# crt13n.net
KiCad netlist of a schematic drawn in EAGLE
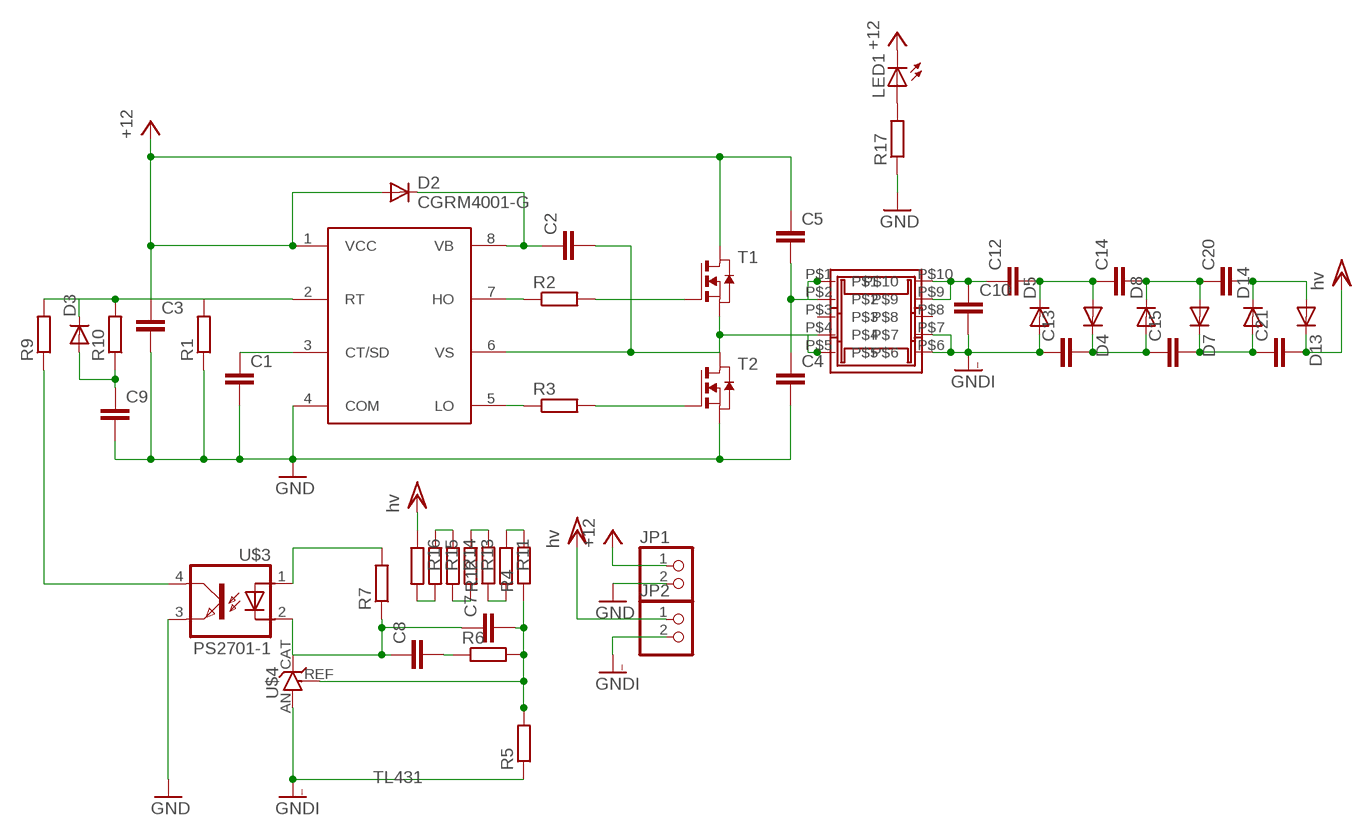
[diagram p0: schematic, sheet 1]

(export (version "E")
  (design (tool "Eeschema 10.0.6"))
  (components
    (comp (ref "C1")
      (value "C-EUC0805")
      (footprint "eagle-import:C0805")
      (libsource (lib "eagle-import") (part "C-EUC0805"))
    )
    (comp (ref "C2")
      (value "C-EUC0805")
      (footprint "eagle-import:C0805")
      (libsource (lib "eagle-import") (part "C-EUC0805"))
    )
    (comp (ref "C3")
      (value "C-EUC1206")
      (footprint "eagle-import:C1206")
      (libsource (lib "eagle-import") (part "C-EUC1206"))
    )
    (comp (ref "C4")
      (value "CC1206")
      (footprint "eagle-import:C1206")
      (libsource (lib "eagle-import") (part "CC1206"))
    )
    (comp (ref "C5")
      (value "CC1206")
      (footprint "eagle-import:C1206")
      (libsource (lib "eagle-import") (part "CC1206"))
    )
    (comp (ref "C7")
      (value "C-EUC0805")
      (footprint "eagle-import:C0805")
      (libsource (lib "eagle-import") (part "C-EUC0805"))
    )
    (comp (ref "C8")
      (value "C-EUC0805")
      (footprint "eagle-import:C0805")
      (libsource (lib "eagle-import") (part "C-EUC0805"))
    )
    (comp (ref "C9")
      (value "C-EUC1206")
      (footprint "eagle-import:C1206")
      (libsource (lib "eagle-import") (part "C-EUC1206"))
    )
    (comp (ref "C10")
      (value "C-EUC1812")
      (footprint "eagle-import:C1812")
      (libsource (lib "eagle-import") (part "C-EUC1812"))
    )
    (comp (ref "C12")
      (value "C-EUC2220K")
      (footprint "eagle-import:C2220K")
      (libsource (lib "eagle-import") (part "C-EUC2220K"))
    )
    (comp (ref "C13")
      (value "C-EUC2220K")
      (footprint "eagle-import:C2220K")
      (libsource (lib "eagle-import") (part "C-EUC2220K"))
    )
    (comp (ref "C14")
      (value "C-EUC2220K")
      (footprint "eagle-import:C2220K")
      (libsource (lib "eagle-import") (part "C-EUC2220K"))
    )
    (comp (ref "C15")
      (value "C-EUC2220K")
      (footprint "eagle-import:C2220K")
      (libsource (lib "eagle-import") (part "C-EUC2220K"))
    )
    (comp (ref "C20")
      (value "C-EUC2220K")
      (footprint "eagle-import:C2220K")
      (libsource (lib "eagle-import") (part "C-EUC2220K"))
    )
    (comp (ref "C21")
      (value "C-EUC2220K")
      (footprint "eagle-import:C2220K")
      (libsource (lib "eagle-import") (part "C-EUC2220K"))
    )
    (comp (ref "D2")
      (value "CGRM4001-G")
      (footprint "eagle-import:SOD-123_MINI-SMA")
      (libsource (lib "eagle-import") (part "CGRM400-G1"))
    )
    (comp (ref "D3")
      (value "DIODE-SOD80C")
      (footprint "eagle-import:SOD80C")
      (libsource (lib "eagle-import") (part "DIODE-SOD80C"))
    )
    (comp (ref "D4")
      (value "DIODE-DO-214AC")
      (footprint "eagle-import:DO-214AC")
      (libsource (lib "eagle-import") (part "DIODE-DO-214AC"))
    )
    (comp (ref "D5")
      (value "DIODE-DO-214AC")
      (footprint "eagle-import:DO-214AC")
      (libsource (lib "eagle-import") (part "DIODE-DO-214AC"))
    )
    (comp (ref "D7")
      (value "DIODE-DO-214AC")
      (footprint "eagle-import:DO-214AC")
      (libsource (lib "eagle-import") (part "DIODE-DO-214AC"))
    )
    (comp (ref "D8")
      (value "DIODE-DO-214AC")
      (footprint "eagle-import:DO-214AC")
      (libsource (lib "eagle-import") (part "DIODE-DO-214AC"))
    )
    (comp (ref "D13")
      (value "DIODE-DO-214AC")
      (footprint "eagle-import:DO-214AC")
      (libsource (lib "eagle-import") (part "DIODE-DO-214AC"))
    )
    (comp (ref "D14")
      (value "DIODE-DO-214AC")
      (footprint "eagle-import:DO-214AC")
      (libsource (lib "eagle-import") (part "DIODE-DO-214AC"))
    )
    (comp (ref "JP1")
      (value "PINHD-1X2")
      (footprint "eagle-import:1X02")
      (libsource (lib "eagle-import") (part "PINHD-1X2"))
    )
    (comp (ref "JP2")
      (value "PINHD-1X2")
      (footprint "eagle-import:1X02")
      (libsource (lib "eagle-import") (part "PINHD-1X2"))
    )
    (comp (ref "LED1")
      (value "LEDCHIP-LED0805")
      (footprint "eagle-import:CHIP-LED0805")
      (libsource (lib "eagle-import") (part "LEDCHIP-LED0805"))
    )
    (comp (ref "R1")
      (value "R-EU_R0805")
      (footprint "eagle-import:R0805")
      (libsource (lib "eagle-import") (part "R-EU_R0805"))
    )
    (comp (ref "R2")
      (value "R-EU_R0805")
      (footprint "eagle-import:R0805")
      (libsource (lib "eagle-import") (part "R-EU_R0805"))
    )
    (comp (ref "R3")
      (value "R-EU_R0805")
      (footprint "eagle-import:R0805")
      (libsource (lib "eagle-import") (part "R-EU_R0805"))
    )
    (comp (ref "R4")
      (value "R-EU_R0805")
      (footprint "eagle-import:R0805")
      (libsource (lib "eagle-import") (part "R-EU_R0805"))
    )
    (comp (ref "R5")
      (value "R-EU_R0805")
      (footprint "eagle-import:R0805")
      (libsource (lib "eagle-import") (part "R-EU_R0805"))
    )
    (comp (ref "R6")
      (value "R-EU_R0805")
      (footprint "eagle-import:R0805")
      (libsource (lib "eagle-import") (part "R-EU_R0805"))
    )
    (comp (ref "R7")
      (value "R-EU_R0805")
      (footprint "eagle-import:R0805")
      (libsource (lib "eagle-import") (part "R-EU_R0805"))
    )
    (comp (ref "R9")
      (value "R-EU_R0805")
      (footprint "eagle-import:R0805")
      (libsource (lib "eagle-import") (part "R-EU_R0805"))
    )
    (comp (ref "R10")
      (value "R-EU_R0805")
      (footprint "eagle-import:R0805")
      (libsource (lib "eagle-import") (part "R-EU_R0805"))
    )
    (comp (ref "R11")
      (value "R-EU_R0805")
      (footprint "eagle-import:R0805")
      (libsource (lib "eagle-import") (part "R-EU_R0805"))
    )
    (comp (ref "R12")
      (value "R-EU_R0805")
      (footprint "eagle-import:R0805")
      (libsource (lib "eagle-import") (part "R-EU_R0805"))
    )
    (comp (ref "R13")
      (value "R-EU_R0805")
      (footprint "eagle-import:R0805")
      (libsource (lib "eagle-import") (part "R-EU_R0805"))
    )
    (comp (ref "R14")
      (value "R-EU_R0805")
      (footprint "eagle-import:R0805")
      (libsource (lib "eagle-import") (part "R-EU_R0805"))
    )
    (comp (ref "R15")
      (value "R-EU_R0805")
      (footprint "eagle-import:R0805")
      (libsource (lib "eagle-import") (part "R-EU_R0805"))
    )
    (comp (ref "R16")
      (value "R-EU_R0805")
      (footprint "eagle-import:R0805")
      (libsource (lib "eagle-import") (part "R-EU_R0805"))
    )
    (comp (ref "R17")
      (value "R-EU_R0805")
      (footprint "eagle-import:R0805")
      (libsource (lib "eagle-import") (part "R-EU_R0805"))
    )
    (comp (ref "T1")
      (value "NMOSSOT23")
      (footprint "eagle-import:SOT-23")
      (libsource (lib "eagle-import") (part "NMOSSOT23"))
    )
    (comp (ref "T2")
      (value "NMOSSOT23")
      (footprint "eagle-import:SOT-23")
      (libsource (lib "eagle-import") (part "NMOSSOT23"))
    )
    (comp (ref "U$1")
      (value "IRS2795")
      (footprint "eagle-import:SO08")
      (libsource (lib "eagle-import") (part "IRS2795"))
    )
    (comp (ref "U$2")
      (value "EFD15-K-10P")
      (footprint "eagle-import:EFD15-K10P")
      (libsource (lib "eagle-import") (part "EFD15-K-10P"))
    )
    (comp (ref "U$3")
      (value "PS2701-1")
      (footprint "eagle-import:SOP04")
      (libsource (lib "eagle-import") (part "PS2701-1"))
    )
    (comp (ref "U$4")
      (value "TL431")
      (footprint "eagle-import:SOT23")
      (libsource (lib "eagle-import") (part "TL431"))
    )
  )
  (nets
    (net (code "1") (name "+12") (class "Default")
      (node (ref "C3") (pin "1") (pinfunction "1_1") (pintype "passive"))
      (node (ref "C5") (pin "1") (pinfunction "1_1") (pintype "passive"))
      (node (ref "D2") (pin "A") (pinfunction "A_A") (pintype "passive"))
      (node (ref "JP1") (pin "1") (pinfunction "1_1") (pintype "passive"))
      (node (ref "LED1") (pin "C") (pinfunction "C_C") (pintype "passive"))
      (node (ref "T1") (pin "1") (pinfunction "D_1") (pintype "passive"))
      (node (ref "U$1") (pin "1") (pinfunction "VCC_1") (pintype "bidirectional"))
    )
    (net (code "2") (name "GND") (class "Default")
      (node (ref "C1") (pin "2") (pinfunction "2_2") (pintype "passive"))
      (node (ref "C3") (pin "2") (pinfunction "2_2") (pintype "passive"))
      (node (ref "C4") (pin "2") (pinfunction "2_2") (pintype "passive"))
      (node (ref "C9") (pin "2") (pinfunction "2_2") (pintype "passive"))
      (node (ref "JP1") (pin "2") (pinfunction "2_2") (pintype "passive"))
      (node (ref "R1") (pin "1") (pinfunction "1_1") (pintype "passive"))
      (node (ref "R17") (pin "1") (pinfunction "1_1") (pintype "passive"))
      (node (ref "T2") (pin "2") (pinfunction "S_2") (pintype "passive"))
      (node (ref "U$1") (pin "4") (pinfunction "COM_4") (pintype "bidirectional"))
      (node (ref "U$3") (pin "3") (pinfunction "3_3") (pintype "passive"))
    )
    (net (code "3") (name "GNDI") (class "Default")
      (node (ref "C10") (pin "2") (pinfunction "2_2") (pintype "passive"))
      (node (ref "C13") (pin "1") (pinfunction "1_1") (pintype "passive"))
      (node (ref "D5") (pin "A") (pinfunction "A_A") (pintype "passive"))
      (node (ref "JP2") (pin "2") (pinfunction "2_2") (pintype "passive"))
      (node (ref "R5") (pin "1") (pinfunction "1_1") (pintype "passive"))
      (node (ref "U$2") (pin "P$6") (pinfunction "P$6_P$6") (pintype "bidirectional"))
      (node (ref "U$2") (pin "P$7") (pinfunction "P$7_P$7") (pintype "bidirectional"))
      (node (ref "U$4") (pin "AN") (pinfunction "AN_AN") (pintype "passive"))
    )
    (net (code "4") (name "Net-(C4-Pad1)") (class "Default")
      (node (ref "C4") (pin "1") (pinfunction "1_1") (pintype "passive"))
      (node (ref "C5") (pin "2") (pinfunction "2_2") (pintype "passive"))
      (node (ref "U$2") (pin "P$1") (pinfunction "P$1_P$1") (pintype "bidirectional"))
      (node (ref "U$2") (pin "P$2") (pinfunction "P$2_P$2") (pintype "bidirectional"))
    )
    (net (code "5") (name "Net-(C7-Pad1)") (class "Default")
      (node (ref "C7") (pin "1") (pinfunction "1_1") (pintype "passive"))
      (node (ref "C8") (pin "1") (pinfunction "1_1") (pintype "passive"))
      (node (ref "R7") (pin "1") (pinfunction "1_1") (pintype "passive"))
      (node (ref "U$3") (pin "2") (pinfunction "2_2") (pintype "passive"))
      (node (ref "U$4") (pin "CAT") (pinfunction "CAT_CAT") (pintype "passive"))
    )
    (net (code "6") (name "Net-(C7-Pad2)") (class "Default")
      (node (ref "C7") (pin "2") (pinfunction "2_2") (pintype "passive"))
      (node (ref "R4") (pin "1") (pinfunction "1_1") (pintype "passive"))
      (node (ref "R5") (pin "2") (pinfunction "2_2") (pintype "passive"))
      (node (ref "R6") (pin "2") (pinfunction "2_2") (pintype "passive"))
      (node (ref "U$4") (pin "REF") (pinfunction "REF_REF") (pintype "passive"))
    )
    (net (code "7") (name "Net-(C8-Pad2)") (class "Default")
      (node (ref "C8") (pin "2") (pinfunction "2_2") (pintype "passive"))
      (node (ref "R6") (pin "1") (pinfunction "1_1") (pintype "passive"))
    )
    (net (code "8") (name "Net-(C9-Pad1)") (class "Default")
      (node (ref "C9") (pin "1") (pinfunction "1_1") (pintype "passive"))
      (node (ref "D3") (pin "A") (pinfunction "A_A") (pintype "passive"))
      (node (ref "R10") (pin "1") (pinfunction "1_1") (pintype "passive"))
    )
    (net (code "9") (name "Net-(C10-Pad1)") (class "Default")
      (node (ref "C10") (pin "1") (pinfunction "1_1") (pintype "passive"))
      (node (ref "C12") (pin "1") (pinfunction "1_1") (pintype "passive"))
      (node (ref "U$2") (pin "P$10") (pinfunction "P$10_P$10") (pintype "bidirectional"))
      (node (ref "U$2") (pin "P$9") (pinfunction "P$9_P$9") (pintype "bidirectional"))
    )
    (net (code "10") (name "Net-(C12-Pad2)") (class "Default")
      (node (ref "C12") (pin "2") (pinfunction "2_2") (pintype "passive"))
      (node (ref "C14") (pin "1") (pinfunction "1_1") (pintype "passive"))
      (node (ref "D4") (pin "A") (pinfunction "A_A") (pintype "passive"))
      (node (ref "D5") (pin "C") (pinfunction "C_C") (pintype "passive"))
    )
    (net (code "11") (name "Net-(C13-Pad2)") (class "Default")
      (node (ref "C13") (pin "2") (pinfunction "2_2") (pintype "passive"))
      (node (ref "C15") (pin "1") (pinfunction "1_1") (pintype "passive"))
      (node (ref "D4") (pin "C") (pinfunction "C_C") (pintype "passive"))
      (node (ref "D8") (pin "A") (pinfunction "A_A") (pintype "passive"))
    )
    (net (code "12") (name "Net-(C14-Pad2)") (class "Default")
      (node (ref "C14") (pin "2") (pinfunction "2_2") (pintype "passive"))
      (node (ref "C20") (pin "1") (pinfunction "1_1") (pintype "passive"))
      (node (ref "D7") (pin "A") (pinfunction "A_A") (pintype "passive"))
      (node (ref "D8") (pin "C") (pinfunction "C_C") (pintype "passive"))
    )
    (net (code "13") (name "Net-(C15-Pad2)") (class "Default")
      (node (ref "C15") (pin "2") (pinfunction "2_2") (pintype "passive"))
      (node (ref "C21") (pin "1") (pinfunction "1_1") (pintype "passive"))
      (node (ref "D14") (pin "A") (pinfunction "A_A") (pintype "passive"))
      (node (ref "D7") (pin "C") (pinfunction "C_C") (pintype "passive"))
    )
    (net (code "14") (name "Net-(C20-Pad2)") (class "Default")
      (node (ref "C20") (pin "2") (pinfunction "2_2") (pintype "passive"))
      (node (ref "D13") (pin "A") (pinfunction "A_A") (pintype "passive"))
      (node (ref "D14") (pin "C") (pinfunction "C_C") (pintype "passive"))
    )
    (net (code "15") (name "Net-(LED1-PadA)") (class "Default")
      (node (ref "LED1") (pin "A") (pinfunction "A_A") (pintype "passive"))
      (node (ref "R17") (pin "2") (pinfunction "2_2") (pintype "passive"))
    )
    (net (code "16") (name "Net-(R7-Pad2)") (class "Default")
      (node (ref "R7") (pin "2") (pinfunction "2_2") (pintype "passive"))
      (node (ref "U$3") (pin "1") (pinfunction "1_1") (pintype "passive"))
    )
    (net (code "17") (name "Net-(R9-Pad1)") (class "Default")
      (node (ref "R9") (pin "1") (pinfunction "1_1") (pintype "passive"))
      (node (ref "U$3") (pin "4") (pinfunction "4_4") (pintype "passive"))
    )
    (net (code "18") (name "Net-(R11-Pad1)") (class "Default")
      (node (ref "R11") (pin "1") (pinfunction "1_1") (pintype "passive"))
      (node (ref "R4") (pin "2") (pinfunction "2_2") (pintype "passive"))
    )
    (net (code "19") (name "Net-(R11-Pad2)") (class "Default")
      (node (ref "R11") (pin "2") (pinfunction "2_2") (pintype "passive"))
      (node (ref "R12") (pin "1") (pinfunction "1_1") (pintype "passive"))
    )
    (net (code "20") (name "Net-(R12-Pad2)") (class "Default")
      (node (ref "R12") (pin "2") (pinfunction "2_2") (pintype "passive"))
      (node (ref "R13") (pin "1") (pinfunction "1_1") (pintype "passive"))
    )
    (net (code "21") (name "Net-(R13-Pad2)") (class "Default")
      (node (ref "R13") (pin "2") (pinfunction "2_2") (pintype "passive"))
      (node (ref "R14") (pin "2") (pinfunction "2_2") (pintype "passive"))
    )
    (net (code "22") (name "Net-(R14-Pad1)") (class "Default")
      (node (ref "R14") (pin "1") (pinfunction "1_1") (pintype "passive"))
      (node (ref "R15") (pin "1") (pinfunction "1_1") (pintype "passive"))
    )
    (net (code "23") (name "Net-(R15-Pad2)") (class "Default")
      (node (ref "R15") (pin "2") (pinfunction "2_2") (pintype "passive"))
      (node (ref "R16") (pin "2") (pinfunction "2_2") (pintype "passive"))
    )
    (net (code "24") (name "Net-(T1-G)") (class "Default")
      (node (ref "R2") (pin "2") (pinfunction "2_2") (pintype "passive"))
      (node (ref "T1") (pin "3") (pinfunction "G_3") (pintype "passive"))
    )
    (net (code "25") (name "Net-(T1-S)") (class "Default")
      (node (ref "C2") (pin "2") (pinfunction "2_2") (pintype "passive"))
      (node (ref "T1") (pin "2") (pinfunction "S_2") (pintype "passive"))
      (node (ref "T2") (pin "1") (pinfunction "D_1") (pintype "passive"))
      (node (ref "U$1") (pin "6") (pinfunction "VS_6") (pintype "bidirectional"))
      (node (ref "U$2") (pin "P$4") (pinfunction "P$4_P$4") (pintype "bidirectional"))
      (node (ref "U$2") (pin "P$5") (pinfunction "P$5_P$5") (pintype "bidirectional"))
    )
    (net (code "26") (name "Net-(T2-G)") (class "Default")
      (node (ref "R3") (pin "2") (pinfunction "2_2") (pintype "passive"))
      (node (ref "T2") (pin "3") (pinfunction "G_3") (pintype "passive"))
    )
    (net (code "27") (name "Net-(U$1-CT{slash}SD)") (class "Default")
      (node (ref "C1") (pin "1") (pinfunction "1_1") (pintype "passive"))
      (node (ref "U$1") (pin "3") (pinfunction "CT/SD_3") (pintype "bidirectional"))
    )
    (net (code "28") (name "Net-(U$1-HO)") (class "Default")
      (node (ref "R2") (pin "1") (pinfunction "1_1") (pintype "passive"))
      (node (ref "U$1") (pin "7") (pinfunction "HO_7") (pintype "output"))
    )
    (net (code "29") (name "Net-(U$1-LO)") (class "Default")
      (node (ref "R3") (pin "1") (pinfunction "1_1") (pintype "passive"))
      (node (ref "U$1") (pin "5") (pinfunction "LO_5") (pintype "output"))
    )
    (net (code "30") (name "Net-(U$1-RT)") (class "Default")
      (node (ref "D3") (pin "C") (pinfunction "C_C") (pintype "passive"))
      (node (ref "R1") (pin "2") (pinfunction "2_2") (pintype "passive"))
      (node (ref "R10") (pin "2") (pinfunction "2_2") (pintype "passive"))
      (node (ref "R9") (pin "2") (pinfunction "2_2") (pintype "passive"))
      (node (ref "U$1") (pin "2") (pinfunction "RT_2") (pintype "bidirectional"))
    )
    (net (code "31") (name "Net-(U$1-VB)") (class "Default")
      (node (ref "C2") (pin "1") (pinfunction "1_1") (pintype "passive"))
      (node (ref "D2") (pin "C") (pinfunction "C_C") (pintype "passive"))
      (node (ref "U$1") (pin "8") (pinfunction "VB_8") (pintype "bidirectional"))
    )
    (net (code "32") (name "hv") (class "Default")
      (node (ref "C21") (pin "2") (pinfunction "2_2") (pintype "passive"))
      (node (ref "D13") (pin "C") (pinfunction "C_C") (pintype "passive"))
      (node (ref "JP2") (pin "1") (pinfunction "1_1") (pintype "passive"))
      (node (ref "R16") (pin "1") (pinfunction "1_1") (pintype "passive"))
    )
    (net (code "33") (name "unconnected-(U$2-PadP$3)") (class "Default")
      (node (ref "U$2") (pin "P$3") (pinfunction "P$3_P$3") (pintype "bidirectional"))
    )
    (net (code "34") (name "unconnected-(U$2-PadP$8)") (class "Default")
      (node (ref "U$2") (pin "P$8") (pinfunction "P$8_P$8") (pintype "bidirectional"))
    )
  )
)
